# SCH_NIRV2_Driver.net
KiCad netlist of a schematic drawn in EasyEDA
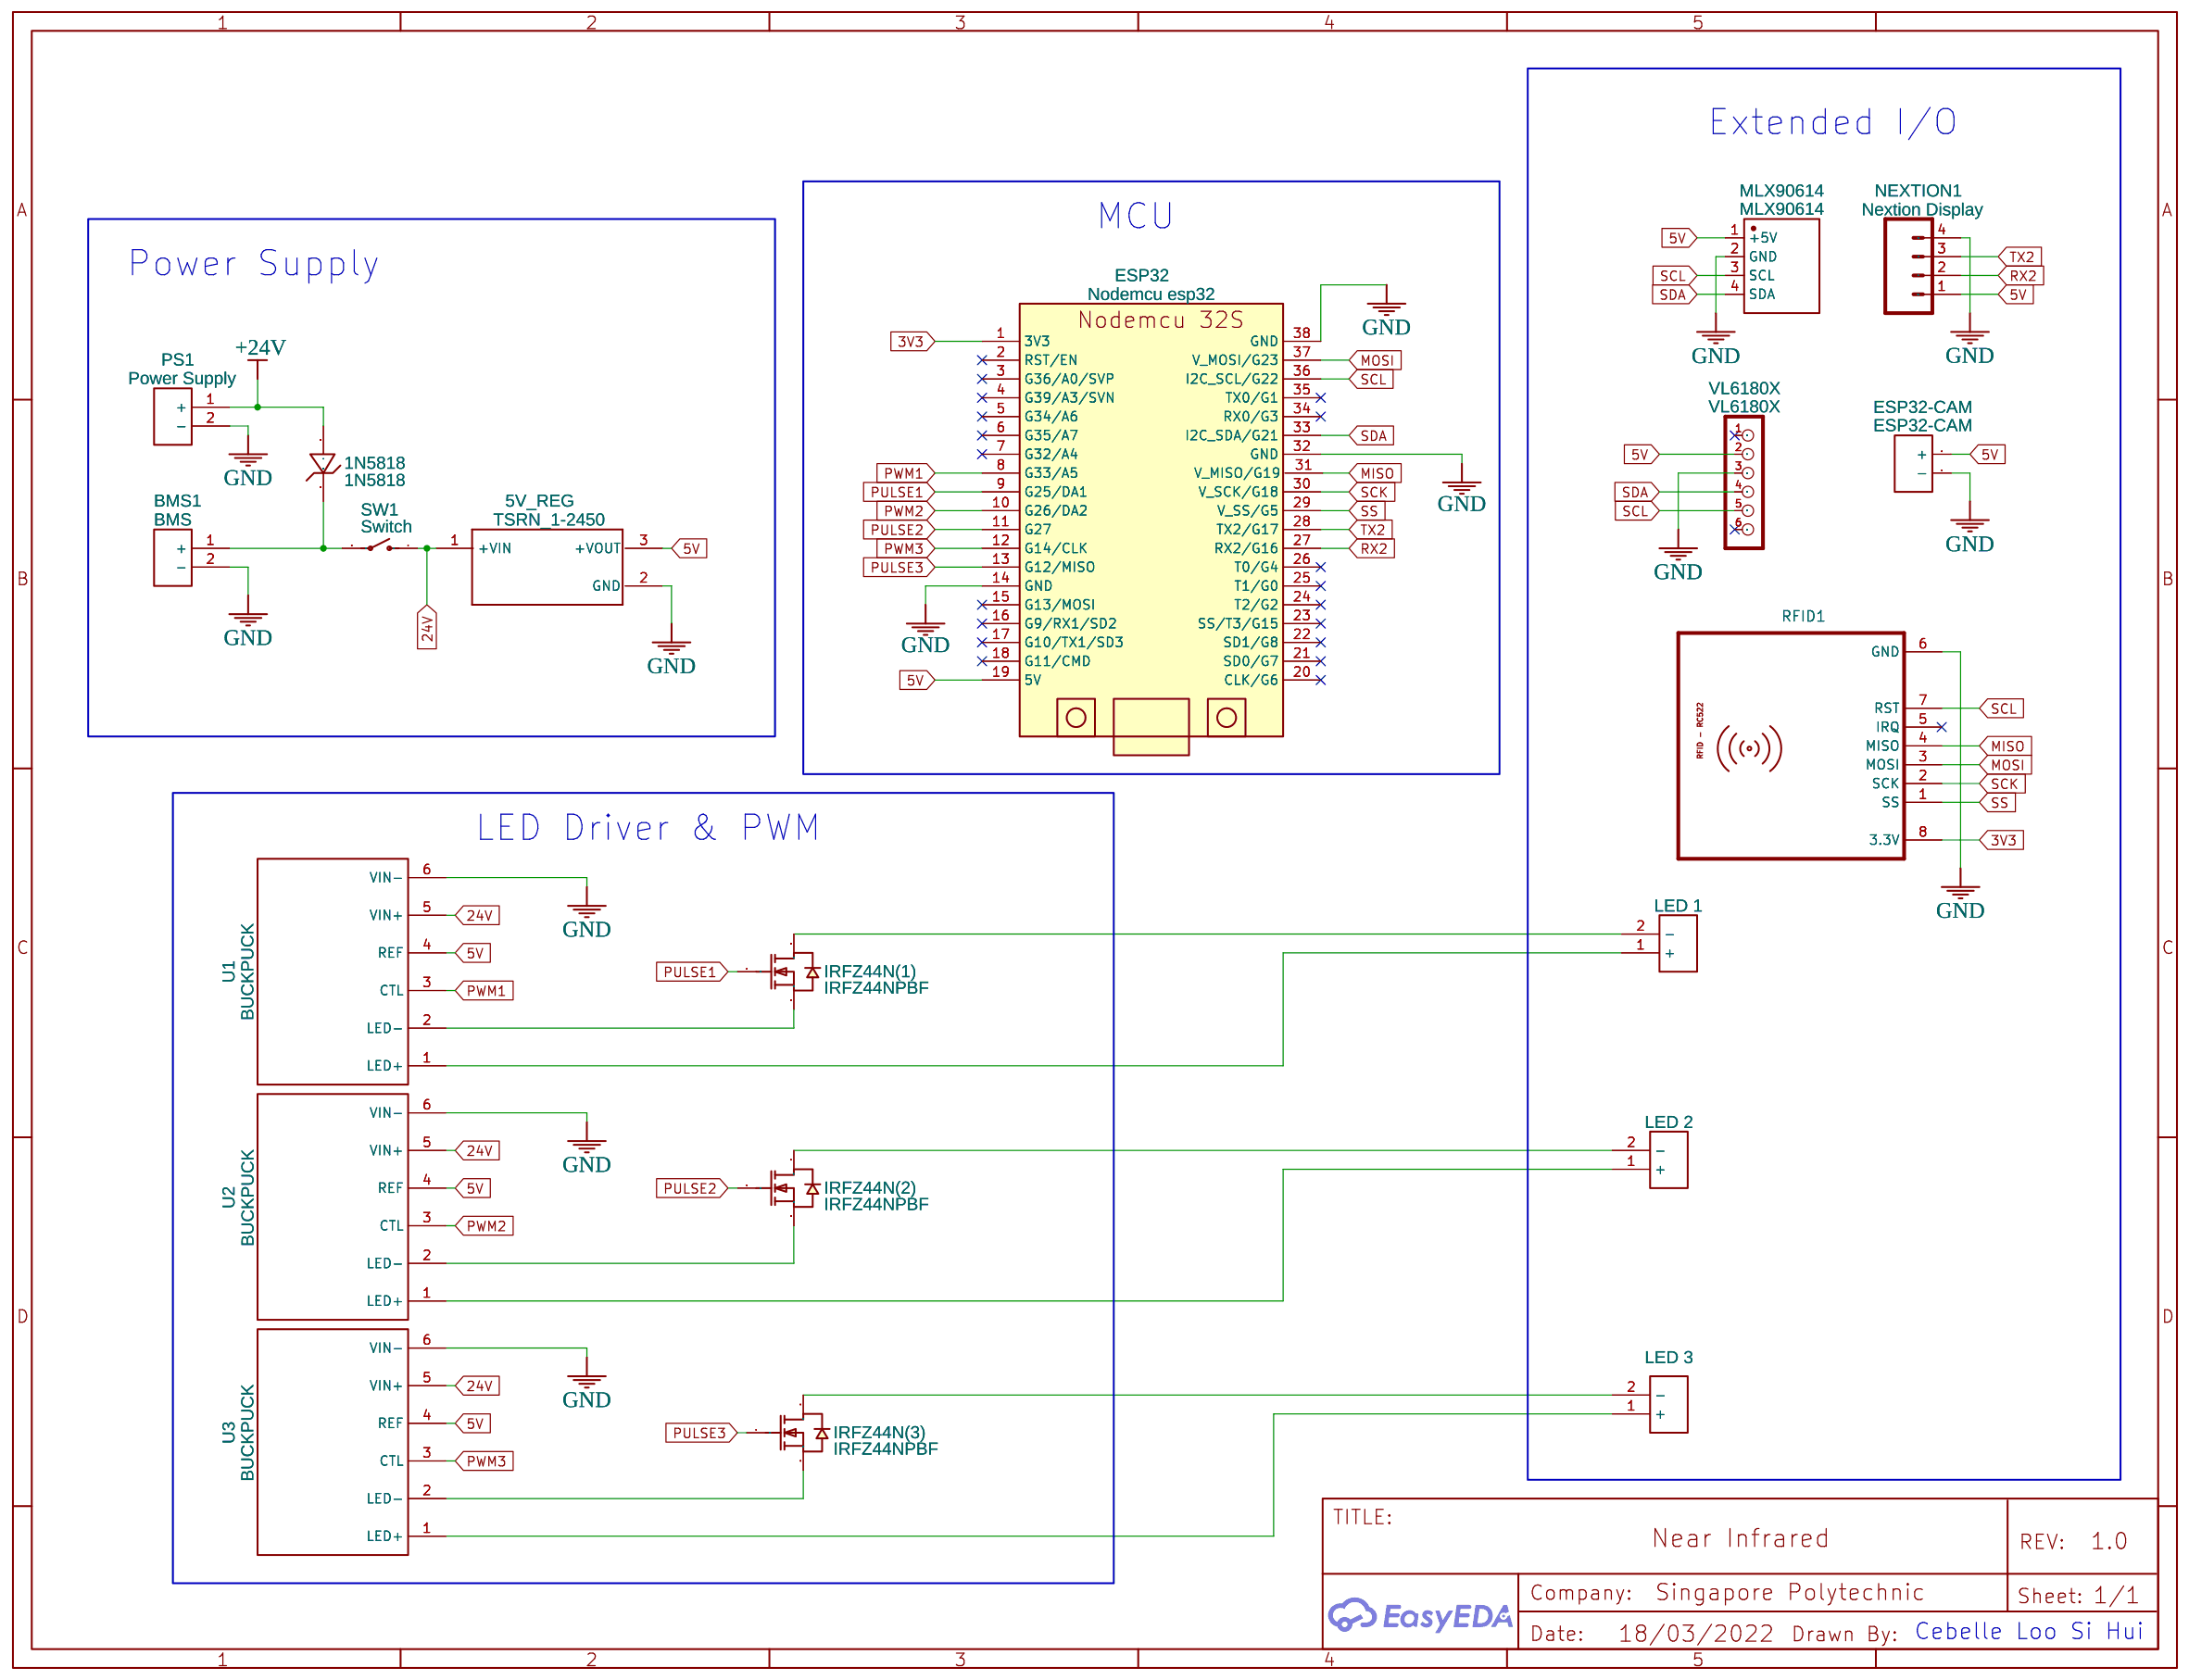
[diagram p0: schematic sheet]

(export (version "E")
  (design (tool "Eeschema 10.0.6"))
  (components
    (comp (ref "1N5818")
      (value "1N5818")
      (fields (field (name "BOM_Supplier Part") "C402217"))
      (libsource (lib "") (part "1N5818"))
    )
    (comp (ref "5V_REG") (value "TSRN_1-2450") (libsource (lib "") (part "TSRN_1-2450")))
    (comp (ref "BMS1")
      (value "BMS")
      (fields
        (field (name "BOM_Manufacturer Part") "WJ103-5.00-2P")
        (field (name "BOM_Supplier Part") "C8439")
      )
      (libsource (lib "") (part "WJ103-5.00-2P_2"))
    )
    (comp (ref "ESP32") (value "Nodemcu esp32") (libsource (lib "") (part "Nodemcu esp32")))
    (comp (ref "ESP32-CAM")
      (value "ESP32-CAM")
      (fields
        (field (name "BOM_Manufacturer Part") "2.54-1*2PFemale")
        (field (name "BOM_Supplier Part") "C49661")
      )
      (libsource (lib "") (part "Header-Female-2.54_1x2"))
    )
    (comp (ref "IRFZ44N(1)")
      (value "IRFZ44NPBF")
      (fields (field (name "BOM_Supplier Part") "C2586"))
      (libsource (lib "") (part "IRFZ44NPBF"))
    )
    (comp (ref "IRFZ44N(2)")
      (value "IRFZ44NPBF")
      (fields (field (name "BOM_Supplier Part") "C2586"))
      (libsource (lib "") (part "IRFZ44NPBF_1"))
    )
    (comp (ref "IRFZ44N(3)")
      (value "IRFZ44NPBF")
      (fields (field (name "BOM_Supplier Part") "C2586"))
      (libsource (lib "") (part "IRFZ44NPBF_2"))
    )
    (comp (ref "LED1")
      (value "LED 1")
      (fields
        (field (name "BOM_Manufacturer Part") "WJ103-5.00-2P")
        (field (name "BOM_Supplier Part") "C8439")
      )
      (libsource (lib "") (part "WJ103-5.00-2P"))
    )
    (comp (ref "LED2")
      (value "LED 2")
      (fields
        (field (name "BOM_Manufacturer Part") "WJ103-5.00-2P")
        (field (name "BOM_Supplier Part") "C8439")
      )
      (libsource (lib "") (part "WJ103-5.00-2P"))
    )
    (comp (ref "LED3")
      (value "LED 3")
      (fields
        (field (name "BOM_Manufacturer Part") "WJ103-5.00-2P")
        (field (name "BOM_Supplier Part") "C8439")
      )
      (libsource (lib "") (part "WJ103-5.00-2P"))
    )
    (comp (ref "MLX90614")
      (value "MLX90614")
      (fields
        (field (name "BOM_Manufacturer Part") "RE-H042TD-1190(LF)(SN)")
        (field (name "BOM_Supplier Part") "C265319")
      )
      (libsource (lib "") (part "RE-H042TD-1190(LF)(SN)"))
    )
    (comp (ref "NEXTION1") (value "Nextion Display") (libsource (lib "") (part "M04POLAR")))
    (comp (ref "PS1")
      (value "Power Supply")
      (fields
        (field (name "BOM_Manufacturer Part") "WJ103-5.00-2P")
        (field (name "BOM_Supplier Part") "C8439")
      )
      (libsource (lib "") (part "WJ103-5.00-2P_1"))
    )
    (comp (ref "RFID1") (value "NO") (libsource (lib "") (part "Unknown_954_-490")))
    (comp (ref "SW1")
      (value "Switch")
      (fields (field (name "BOM_Manufacturer Part") "KCD1-11-1.5x1cm"))
      (libsource (lib "") (part "SWITCH-2P-SPST-Rocker-10x15mm"))
    )
    (comp (ref "U1") (value "BUCKPUCK") (libsource (lib "") (part "BUCKPUCK")))
    (comp (ref "U2") (value "BUCKPUCK") (libsource (lib "") (part "BUCKPUCK")))
    (comp (ref "U3") (value "BUCKPUCK") (libsource (lib "") (part "BUCKPUCK")))
    (comp (ref "VL6180X") (value "VL6180X") (libsource (lib "") (part "CON_HEADER_1X06-PTH")))
  )
  (nets
    (net (code "1") (name "+24V") (class "Default")
      (node (ref "1N5818") (pin "2") (pinfunction "A_2") (pintype "unspecified"))
      (node (ref "PS1") (pin "1") (pinfunction "+_1") (pintype "unspecified"))
    )
    (net (code "2") (name "3V3") (class "Default")
      (node (ref "ESP32") (pin "1") (pinfunction "3V3_1") (pintype "passive"))
      (node (ref "RFID1") (pin "8") (pinfunction "3.3V_8") (pintype "unspecified"))
    )
    (net (code "3") (name "5V") (class "Default")
      (node (ref "5V_REG") (pin "3") (pinfunction "+VOUT_3") (pintype "bidirectional"))
      (node (ref "ESP32") (pin "19") (pinfunction "5V_19") (pintype "passive"))
      (node (ref "ESP32-CAM") (pin "2") (pinfunction "+_2") (pintype "input"))
      (node (ref "MLX90614") (pin "1") (pinfunction "+5V_1") (pintype "unspecified"))
      (node (ref "NEXTION1") (pin "1") (pinfunction "GND_1") (pintype "unspecified"))
      (node (ref "U1") (pin "4") (pinfunction "REF_4") (pintype "unspecified"))
      (node (ref "U2") (pin "4") (pinfunction "REF_4") (pintype "unspecified"))
      (node (ref "U3") (pin "4") (pinfunction "REF_4") (pintype "unspecified"))
      (node (ref "VL6180X") (pin "2") (pinfunction "VIN_2") (pintype "unspecified"))
    )
    (net (code "4") (name "24V") (class "Default")
      (node (ref "5V_REG") (pin "1") (pinfunction "+VIN_1") (pintype "bidirectional"))
      (node (ref "SW1") (pin "1") (pinfunction "O_1") (pintype "unspecified"))
      (node (ref "U1") (pin "5") (pinfunction "VIN+_5") (pintype "unspecified"))
      (node (ref "U2") (pin "5") (pinfunction "VIN+_5") (pintype "unspecified"))
      (node (ref "U3") (pin "5") (pinfunction "VIN+_5") (pintype "unspecified"))
    )
    (net (code "5") (name "GND") (class "Default")
      (node (ref "5V_REG") (pin "2") (pinfunction "GND_2") (pintype "bidirectional"))
      (node (ref "BMS1") (pin "2") (pinfunction "-_2") (pintype "unspecified"))
      (node (ref "ESP32") (pin "14") (pinfunction "GND_14") (pintype "passive"))
      (node (ref "ESP32") (pin "32") (pinfunction "GND_32") (pintype "passive"))
      (node (ref "ESP32") (pin "38") (pinfunction "GND_38") (pintype "passive"))
      (node (ref "ESP32-CAM") (pin "1") (pinfunction "-_1") (pintype "input"))
      (node (ref "MLX90614") (pin "2") (pinfunction "GND_2") (pintype "unspecified"))
      (node (ref "NEXTION1") (pin "4") (pinfunction "+5V_4") (pintype "unspecified"))
      (node (ref "PS1") (pin "2") (pinfunction "-_2") (pintype "unspecified"))
      (node (ref "RFID1") (pin "6") (pinfunction "GND_6") (pintype "unspecified"))
      (node (ref "U1") (pin "6") (pinfunction "VIN-_6") (pintype "unspecified"))
      (node (ref "U2") (pin "6") (pinfunction "VIN-_6") (pintype "unspecified"))
      (node (ref "U3") (pin "6") (pinfunction "VIN-_6") (pintype "unspecified"))
      (node (ref "VL6180X") (pin "3") (pinfunction "GND_3") (pintype "unspecified"))
    )
    (net (code "6") (name "MISO") (class "Default")
      (node (ref "ESP32") (pin "31") (pinfunction "V_MISO/G19_31") (pintype "bidirectional"))
      (node (ref "RFID1") (pin "4") (pinfunction "MISO_4") (pintype "unspecified"))
    )
    (net (code "7") (name "MOSI") (class "Default")
      (node (ref "ESP32") (pin "37") (pinfunction "V_MOSI/G23_37") (pintype "bidirectional"))
      (node (ref "RFID1") (pin "3") (pinfunction "MOSI_3") (pintype "unspecified"))
    )
    (net (code "8") (name "Net-(1N5818-C)") (class "Default")
      (node (ref "1N5818") (pin "1") (pinfunction "C_1") (pintype "unspecified"))
      (node (ref "BMS1") (pin "1") (pinfunction "+_1") (pintype "unspecified"))
      (node (ref "SW1") (pin "2") (pinfunction "P_2") (pintype "unspecified"))
    )
    (net (code "9") (name "Net-(IRFZ44N(1)-D)") (class "Default")
      (node (ref "IRFZ44N(1)") (pin "2") (pinfunction "D_2") (pintype "unspecified"))
      (node (ref "LED1") (pin "2") (pinfunction "-_2") (pintype "unspecified"))
    )
    (net (code "10") (name "Net-(IRFZ44N(1)-S)") (class "Default")
      (node (ref "IRFZ44N(1)") (pin "3") (pinfunction "S_3") (pintype "unspecified"))
      (node (ref "U1") (pin "2") (pinfunction "LED-_2") (pintype "unspecified"))
    )
    (net (code "11") (name "Net-(IRFZ44N(2)-D)") (class "Default")
      (node (ref "IRFZ44N(2)") (pin "2") (pinfunction "D_2") (pintype "unspecified"))
      (node (ref "LED2") (pin "2") (pinfunction "-_2") (pintype "unspecified"))
    )
    (net (code "12") (name "Net-(IRFZ44N(2)-S)") (class "Default")
      (node (ref "IRFZ44N(2)") (pin "3") (pinfunction "S_3") (pintype "unspecified"))
      (node (ref "U2") (pin "2") (pinfunction "LED-_2") (pintype "unspecified"))
    )
    (net (code "13") (name "Net-(IRFZ44N(3)-D)") (class "Default")
      (node (ref "IRFZ44N(3)") (pin "2") (pinfunction "D_2") (pintype "unspecified"))
      (node (ref "LED3") (pin "2") (pinfunction "-_2") (pintype "unspecified"))
    )
    (net (code "14") (name "Net-(IRFZ44N(3)-S)") (class "Default")
      (node (ref "IRFZ44N(3)") (pin "3") (pinfunction "S_3") (pintype "unspecified"))
      (node (ref "U3") (pin "2") (pinfunction "LED-_2") (pintype "unspecified"))
    )
    (net (code "15") (name "Net-(LED1-+)") (class "Default")
      (node (ref "LED1") (pin "1") (pinfunction "+_1") (pintype "unspecified"))
      (node (ref "U1") (pin "1") (pinfunction "LED+_1") (pintype "unspecified"))
    )
    (net (code "16") (name "Net-(LED2-+)") (class "Default")
      (node (ref "LED2") (pin "1") (pinfunction "+_1") (pintype "unspecified"))
      (node (ref "U2") (pin "1") (pinfunction "LED+_1") (pintype "unspecified"))
    )
    (net (code "17") (name "Net-(LED3-+)") (class "Default")
      (node (ref "LED3") (pin "1") (pinfunction "+_1") (pintype "unspecified"))
      (node (ref "U3") (pin "1") (pinfunction "LED+_1") (pintype "unspecified"))
    )
    (net (code "18") (name "PULSE1") (class "Default")
      (node (ref "ESP32") (pin "9") (pinfunction "G25/DA1_9") (pintype "bidirectional"))
      (node (ref "IRFZ44N(1)") (pin "1") (pinfunction "G_1") (pintype "unspecified"))
    )
    (net (code "19") (name "PULSE2") (class "Default")
      (node (ref "ESP32") (pin "11") (pinfunction "G27_11") (pintype "bidirectional"))
      (node (ref "IRFZ44N(2)") (pin "1") (pinfunction "G_1") (pintype "unspecified"))
    )
    (net (code "20") (name "PULSE3") (class "Default")
      (node (ref "ESP32") (pin "13") (pinfunction "G12/MISO_13") (pintype "bidirectional"))
      (node (ref "IRFZ44N(3)") (pin "1") (pinfunction "G_1") (pintype "unspecified"))
    )
    (net (code "21") (name "PWM1") (class "Default")
      (node (ref "ESP32") (pin "8") (pinfunction "G33/A5_8") (pintype "bidirectional"))
      (node (ref "U1") (pin "3") (pinfunction "CTL_3") (pintype "unspecified"))
    )
    (net (code "22") (name "PWM2") (class "Default")
      (node (ref "ESP32") (pin "10") (pinfunction "G26/DA2_10") (pintype "bidirectional"))
      (node (ref "U2") (pin "3") (pinfunction "CTL_3") (pintype "unspecified"))
    )
    (net (code "23") (name "PWM3") (class "Default")
      (node (ref "ESP32") (pin "12") (pinfunction "G14/CLK_12") (pintype "bidirectional"))
      (node (ref "U3") (pin "3") (pinfunction "CTL_3") (pintype "unspecified"))
    )
    (net (code "24") (name "RX2") (class "Default")
      (node (ref "ESP32") (pin "27") (pinfunction "RX2/G16_27") (pintype "bidirectional"))
      (node (ref "NEXTION1") (pin "2") (pinfunction "RX_2") (pintype "unspecified"))
    )
    (net (code "25") (name "SCK") (class "Default")
      (node (ref "ESP32") (pin "30") (pinfunction "V_SCK/G18_30") (pintype "bidirectional"))
      (node (ref "RFID1") (pin "2") (pinfunction "SCK_2") (pintype "unspecified"))
    )
    (net (code "26") (name "SCL") (class "Default")
      (node (ref "ESP32") (pin "36") (pinfunction "I2C_SCL/G22_36") (pintype "bidirectional"))
      (node (ref "MLX90614") (pin "3") (pinfunction "SCL_3") (pintype "unspecified"))
      (node (ref "RFID1") (pin "7") (pinfunction "RST_7") (pintype "unspecified"))
      (node (ref "VL6180X") (pin "5") (pinfunction "SCL_5") (pintype "unspecified"))
    )
    (net (code "27") (name "SDA") (class "Default")
      (node (ref "ESP32") (pin "33") (pinfunction "I2C_SDA/G21_33") (pintype "bidirectional"))
      (node (ref "MLX90614") (pin "4") (pinfunction "SDA_4") (pintype "unspecified"))
      (node (ref "VL6180X") (pin "4") (pinfunction "SDA_4") (pintype "unspecified"))
    )
    (net (code "28") (name "SS") (class "Default")
      (node (ref "ESP32") (pin "29") (pinfunction "V_SS/G5_29") (pintype "bidirectional"))
      (node (ref "RFID1") (pin "1") (pinfunction "SS_1") (pintype "unspecified"))
    )
    (net (code "29") (name "TX2") (class "Default")
      (node (ref "ESP32") (pin "28") (pinfunction "TX2/G17_28") (pintype "bidirectional"))
      (node (ref "NEXTION1") (pin "3") (pinfunction "TX_3") (pintype "unspecified"))
    )
    (net (code "30") (name "unconnected-(ESP32-CLK{slash}G6-Pad20)") (class "Default")
      (node (ref "ESP32") (pin "20") (pinfunction "CLK/G6_20") (pintype "bidirectional+no_connect"))
    )
    (net (code "31") (name "unconnected-(ESP32-G9{slash}RX1{slash}SD2-Pad16)") (class "Default")
      (node (ref "ESP32") (pin "16") (pinfunction "G9/RX1/SD2_16") (pintype "bidirectional+no_connect"))
    )
    (net (code "32") (name "unconnected-(ESP32-G10{slash}TX1{slash}SD3-Pad17)") (class "Default")
      (node (ref "ESP32") (pin "17") (pinfunction "G10/TX1/SD3_17") (pintype "bidirectional+no_connect"))
    )
    (net (code "33") (name "unconnected-(ESP32-G11{slash}CMD-Pad18)") (class "Default")
      (node (ref "ESP32") (pin "18") (pinfunction "G11/CMD_18") (pintype "bidirectional+no_connect"))
    )
    (net (code "34") (name "unconnected-(ESP32-G13{slash}MOSI-Pad15)") (class "Default")
      (node (ref "ESP32") (pin "15") (pinfunction "G13/MOSI_15") (pintype "bidirectional+no_connect"))
    )
    (net (code "35") (name "unconnected-(ESP32-G32{slash}A4-Pad7)") (class "Default")
      (node (ref "ESP32") (pin "7") (pinfunction "G32/A4_7") (pintype "bidirectional+no_connect"))
    )
    (net (code "36") (name "unconnected-(ESP32-G34{slash}A6-Pad5)") (class "Default")
      (node (ref "ESP32") (pin "5") (pinfunction "G34/A6_5") (pintype "bidirectional+no_connect"))
    )
    (net (code "37") (name "unconnected-(ESP32-G35{slash}A7-Pad6)") (class "Default")
      (node (ref "ESP32") (pin "6") (pinfunction "G35/A7_6") (pintype "bidirectional+no_connect"))
    )
    (net (code "38") (name "unconnected-(ESP32-G36{slash}A0{slash}SVP-Pad3)") (class "Default")
      (node (ref "ESP32") (pin "3") (pinfunction "G36/A0/SVP_3") (pintype "bidirectional+no_connect"))
    )
    (net (code "39") (name "unconnected-(ESP32-G39{slash}A3{slash}SVN-Pad4)") (class "Default")
      (node (ref "ESP32") (pin "4") (pinfunction "G39/A3/SVN_4") (pintype "bidirectional+no_connect"))
    )
    (net (code "40") (name "unconnected-(ESP32-RST{slash}EN-Pad2)") (class "Default")
      (node (ref "ESP32") (pin "2") (pinfunction "RST/EN_2") (pintype "bidirectional+no_connect"))
    )
    (net (code "41") (name "unconnected-(ESP32-RX0{slash}G3-Pad34)") (class "Default")
      (node (ref "ESP32") (pin "34") (pinfunction "RX0/G3_34") (pintype "bidirectional+no_connect"))
    )
    (net (code "42") (name "unconnected-(ESP32-SD0{slash}G7-Pad21)") (class "Default")
      (node (ref "ESP32") (pin "21") (pinfunction "SD0/G7_21") (pintype "bidirectional+no_connect"))
    )
    (net (code "43") (name "unconnected-(ESP32-SD1{slash}G8-Pad22)") (class "Default")
      (node (ref "ESP32") (pin "22") (pinfunction "SD1/G8_22") (pintype "bidirectional+no_connect"))
    )
    (net (code "44") (name "unconnected-(ESP32-SS{slash}T3{slash}G15-Pad23)") (class "Default")
      (node (ref "ESP32") (pin "23") (pinfunction "SS/T3/G15_23") (pintype "bidirectional+no_connect"))
    )
    (net (code "45") (name "unconnected-(ESP32-T0{slash}G4-Pad26)") (class "Default")
      (node (ref "ESP32") (pin "26") (pinfunction "T0/G4_26") (pintype "bidirectional+no_connect"))
    )
    (net (code "46") (name "unconnected-(ESP32-T1{slash}G0-Pad25)") (class "Default")
      (node (ref "ESP32") (pin "25") (pinfunction "T1/G0_25") (pintype "bidirectional+no_connect"))
    )
    (net (code "47") (name "unconnected-(ESP32-T2{slash}G2-Pad24)") (class "Default")
      (node (ref "ESP32") (pin "24") (pinfunction "T2/G2_24") (pintype "bidirectional+no_connect"))
    )
    (net (code "48") (name "unconnected-(ESP32-TX0{slash}G1-Pad35)") (class "Default")
      (node (ref "ESP32") (pin "35") (pinfunction "TX0/G1_35") (pintype "bidirectional+no_connect"))
    )
    (net (code "49") (name "unconnected-(RFID1-IRQ-Pad5)") (class "Default")
      (node (ref "RFID1") (pin "5") (pinfunction "IRQ_5") (pintype "unspecified+no_connect"))
    )
    (net (code "50") (name "unconnected-(VL6180X-IO1-Pad6)") (class "Default")
      (node (ref "VL6180X") (pin "6") (pinfunction "IO1_6") (pintype "unspecified+no_connect"))
    )
    (net (code "51") (name "unconnected-(VL6180X-VDD-Pad1)") (class "Default")
      (node (ref "VL6180X") (pin "1") (pinfunction "VDD_1") (pintype "unspecified+no_connect"))
    )
  )
)
